# VoltageRegulator.net
KiCad netlist of a schematic drawn in Altium Designer
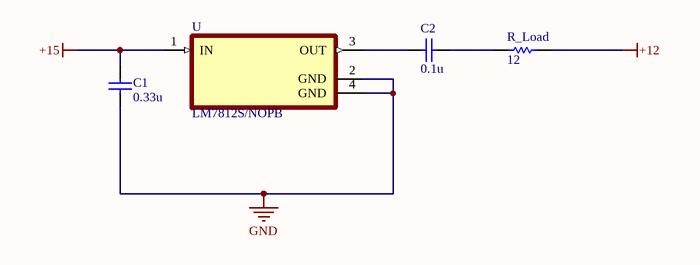
[diagram p0: VoltageRegulator.SchDoc]

(export (version "E")
  (design (tool "Eeschema 10.0.6"))
  (components
    (comp (ref "C1")
      (value "0.33u")
      (description "Capacitor")
      (libsource (lib "Simulation Generic Components") (part "Capacitor"))
    )
    (comp (ref "C2")
      (value "0.1u")
      (description "Capacitor")
      (libsource (lib "Simulation Generic Components") (part "Capacitor"))
    )
    (comp (ref "R_Load")
      (value "12")
      (description "Resistor")
      (libsource (lib "Simulation Generic Components") (part "Resistor"))
    )
    (comp (ref "U")
      (value "LM7812S/NOPB")
      (footprint "TO254P1524X483-4N")
      (description "1.5-A, 30-V, linear voltage regulator 3-DDPAK/TO-263 0 to 125")
      (fields (field (name "MF") "Texas Instruments"))
      (libsource (lib "LM7812S_NOPB") (part "LM7812S/NOPB"))
    )
  )
  (nets
    (net (code "1") (name "+12") (class "Default")
      (node (ref "R_Load") (pin "2") (pinfunction "2_2") (pintype "passive"))
    )
    (net (code "2") (name "+15") (class "Default")
      (node (ref "C1") (pin "2") (pinfunction "2_2") (pintype "passive"))
      (node (ref "U") (pin "1") (pinfunction "IN_1") (pintype "input"))
    )
    (net (code "3") (name "GND") (class "Default")
      (node (ref "C1") (pin "1") (pinfunction "1_1") (pintype "passive"))
      (node (ref "U") (pin "2") (pinfunction "GND_2") (pintype "power_in"))
      (node (ref "U") (pin "4") (pinfunction "GND_4") (pintype "power_in"))
    )
    (net (code "4") (name "Net-(C2-Pad2)") (class "Default")
      (node (ref "C2") (pin "2") (pinfunction "2_2") (pintype "passive"))
      (node (ref "R_Load") (pin "1") (pinfunction "1_1") (pintype "passive"))
    )
    (net (code "5") (name "Net-(U-OUT)") (class "Default")
      (node (ref "C2") (pin "1") (pinfunction "1_1") (pintype "passive"))
      (node (ref "U") (pin "3") (pinfunction "OUT_3") (pintype "output"))
    )
  )
)
